# 2_MicroController.net
KiCad netlist of a schematic drawn in Altium Designer
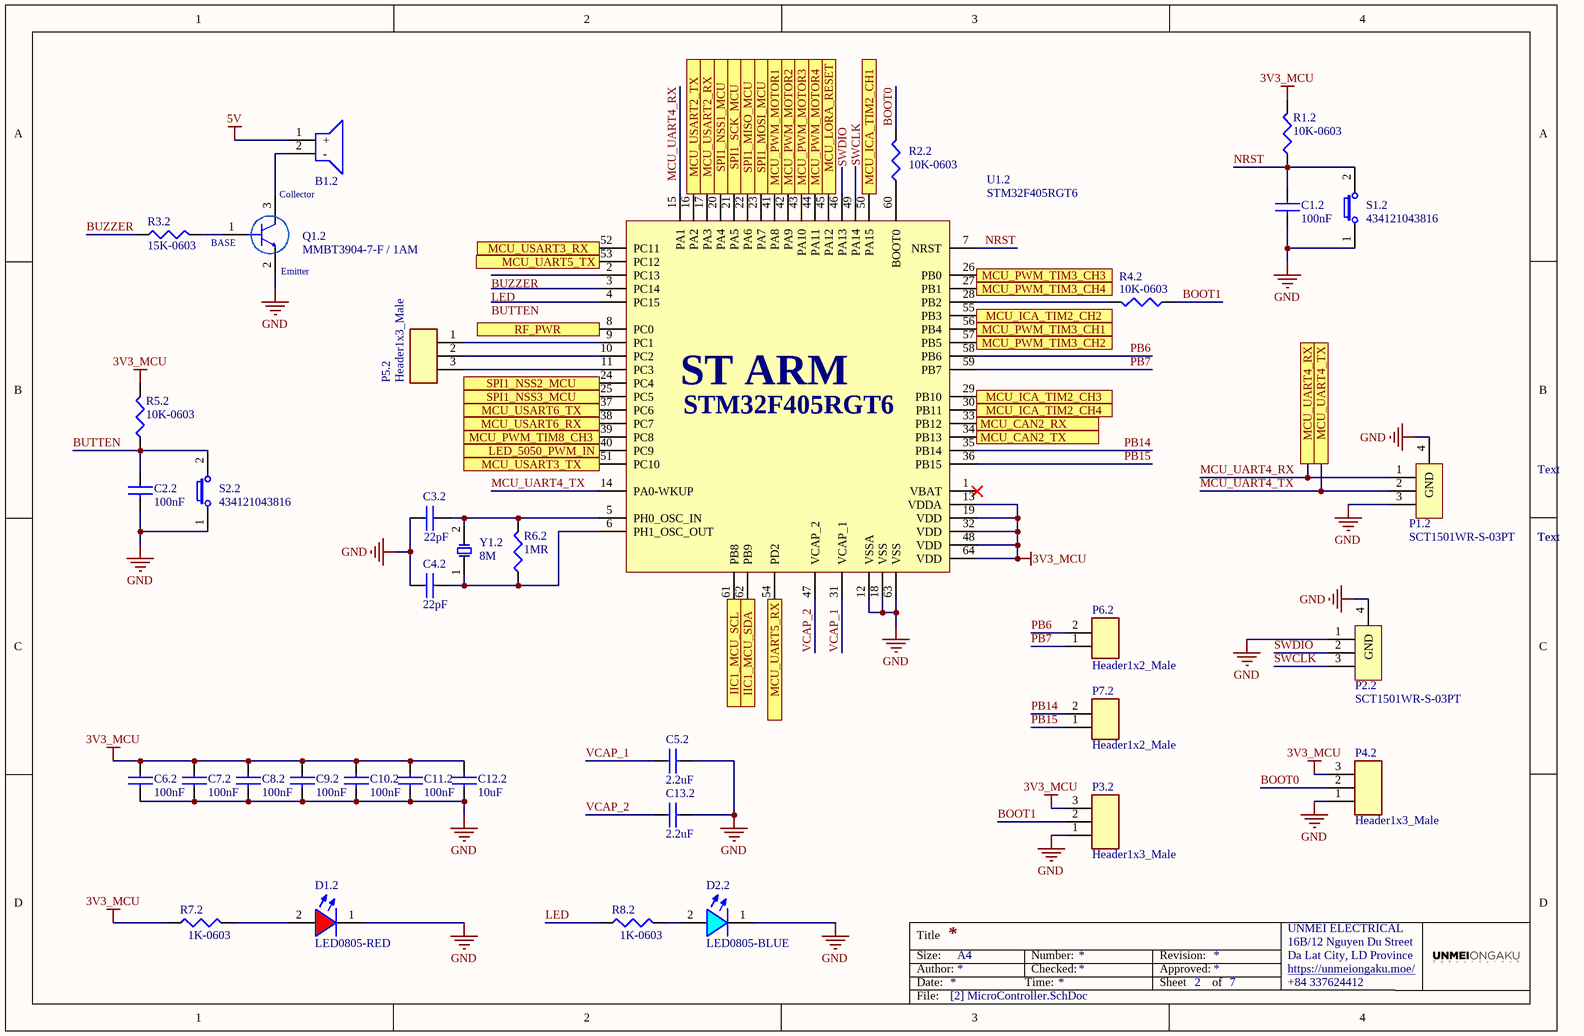
[diagram p0: [2] MicroController.SchDoc]

(export (version "E")
  (design (tool "Eeschema 10.0.6"))
  (components
    (comp (ref "B1.2")
      (value "Buzzer")
      (footprint "Buzzer 9x5mm 60dB")
      (description "9050 DIP Buzzer 9x5mm 60dB")
      (fields (field (name "LOCAL SUPPLIER PART NUMBER") "1209 DIP Buzzer 12x9mm"))
      (libsource (lib "Minh_Lib") (part "Buzzer 9050 - DIP"))
    )
    (comp (ref "C1.2")
      (value "100nF")
      (footprint "CAP0603")
      (description "CAP CER 0.1UF 50V X7R 0603")
      (fields (field (name "TOLERANCE") "±10%"))
      (libsource (lib "Minh_Lib") (part "CC0603KRX7R9BB104"))
    )
    (comp (ref "C2.2")
      (value "100nF")
      (footprint "CAP0603")
      (description "CAP CER 0.1UF 50V X7R 0603")
      (fields (field (name "TOLERANCE") "±10%"))
      (libsource (lib "Minh_Lib") (part "CC0603KRX7R9BB104"))
    )
    (comp (ref "C3.2")
      (value "22pF")
      (footprint "CAP0603")
      (description "Surface Mount Ceramic Multilayer Capacitor 22pF 5% C0G 50V 0603 Paper T/R")
      (fields
        (field (name "MANUFACTURER") "Yageo")
        (field (name "MANUFACTURER PART NUMBER") "CC0603JRNPO9BN220")
      )
      (libsource (lib "Minh_Lib") (part "CC0603JRNPO9BN220"))
    )
    (comp (ref "C4.2")
      (value "22pF")
      (footprint "CAP0603")
      (description "Surface Mount Ceramic Multilayer Capacitor 22pF 5% C0G 50V 0603 Paper T/R")
      (fields
        (field (name "MANUFACTURER") "Yageo")
        (field (name "MANUFACTURER PART NUMBER") "CC0603JRNPO9BN220")
      )
      (libsource (lib "Minh_Lib") (part "CC0603JRNPO9BN220"))
    )
    (comp (ref "C5.2")
      (value "2.2uF")
      (footprint "CAP0603")
      (description "CAP CER 2.2UF 10V X7R 0603")
      (fields (field (name "TOLERANCE") "±10%"))
      (libsource (lib "Minh_Lib") (part "CC0603KRX7R6BB225"))
    )
    (comp (ref "C6.2")
      (value "100nF")
      (footprint "CAP0603")
      (description "CAP CER 0.1UF 50V X7R 0603")
      (fields (field (name "TOLERANCE") "±10%"))
      (libsource (lib "Minh_Lib") (part "CC0603KRX7R9BB104"))
    )
    (comp (ref "C7.2")
      (value "100nF")
      (footprint "CAP0603")
      (description "CAP CER 0.1UF 50V X7R 0603")
      (fields (field (name "TOLERANCE") "±10%"))
      (libsource (lib "Minh_Lib") (part "CC0603KRX7R9BB104"))
    )
    (comp (ref "C8.2")
      (value "100nF")
      (footprint "CAP0603")
      (description "CAP CER 0.1UF 50V X7R 0603")
      (fields (field (name "TOLERANCE") "±10%"))
      (libsource (lib "Minh_Lib") (part "CC0603KRX7R9BB104"))
    )
    (comp (ref "C9.2")
      (value "100nF")
      (footprint "CAP0603")
      (description "CAP CER 0.1UF 50V X7R 0603")
      (fields (field (name "TOLERANCE") "±10%"))
      (libsource (lib "Minh_Lib") (part "CC0603KRX7R9BB104"))
    )
    (comp (ref "C10.2")
      (value "100nF")
      (footprint "CAP0603")
      (description "CAP CER 0.1UF 50V X7R 0603")
      (fields (field (name "TOLERANCE") "±10%"))
      (libsource (lib "Minh_Lib") (part "CC0603KRX7R9BB104"))
    )
    (comp (ref "C11.2")
      (value "100nF")
      (footprint "CAP0603")
      (description "CAP CER 0.1UF 50V X7R 0603")
      (fields (field (name "TOLERANCE") "±10%"))
      (libsource (lib "Minh_Lib") (part "CC0603KRX7R9BB104"))
    )
    (comp (ref "C12.2")
      (value "10uF")
      (footprint "CAP0603")
      (description "CAP CER 10UF 10V X5R 0603")
      (fields (field (name "TOLERANCE") "±10%"))
      (libsource (lib "Minh_Lib") (part "CC0603KRX5R6BB106"))
    )
    (comp (ref "C13.2")
      (value "2.2uF")
      (footprint "CAP0603")
      (description "CAP CER 2.2UF 10V X7R 0603")
      (fields (field (name "TOLERANCE") "±10%"))
      (libsource (lib "Minh_Lib") (part "CC0603KRX7R6BB225"))
    )
    (comp (ref "D1.2")
      (value "LED0805-RED")
      (footprint "LED0805-RED")
      (libsource (lib "Minh_Lib") (part "LED0805-RED"))
    )
    (comp (ref "D2.2")
      (value "LED0805-BLUE")
      (footprint "LED0805-BLUE")
      (libsource (lib "Minh_Lib") (part "LED0805-BLUE"))
    )
    (comp (ref "P1.2")
      (value "SCT1501WR-S-03PT")
      (footprint "Connector ZH1.5 3P SMD")
      (libsource (lib "Minh_Lib") (part "SCT1501WR-S-03PT"))
    )
    (comp (ref "P2.2")
      (value "SCT1501WR-S-03PT")
      (footprint "Connector ZH1.5 3P SMD")
      (libsource (lib "Minh_Lib") (part "SCT1501WR-S-03PT"))
    )
    (comp (ref "P3.2")
      (value "Header1x3_Male")
      (footprint "Minh_Lib:HDR1x3_2.54_MALE")
      (description "Header1x3_2.54_MALE")
      (libsource (lib "") (part "HDR1x3_2.54_MALE_1"))
    )
    (comp (ref "P4.2")
      (value "Header1x3_Male")
      (footprint "Minh_Lib:HDR1x3_2.54_MALE")
      (description "Header1x3_2.54_MALE")
      (libsource (lib "") (part "HDR1x3_2.54_MALE_1"))
    )
    (comp (ref "P5.2")
      (value "Header1x3_Male")
      (footprint "Minh_Lib:HDR1x3_2.54_MALE")
      (description "Header1x3_2.54_MALE")
      (libsource (lib "Minh_Lib") (part "HDR1x3_2.54_MALE"))
    )
    (comp (ref "P6.2")
      (value "Header1x2_Male")
      (footprint "Minh_Lib:HDR1x2_2.54_MALE")
      (description "Header1x2_2.54_MALE")
      (libsource (lib "Minh_Lib") (part "HDR1x2_2.54_MALE"))
    )
    (comp (ref "P7.2")
      (value "Header1x2_Male")
      (footprint "Minh_Lib:HDR1x2_2.54_MALE")
      (description "Header1x2_2.54_MALE")
      (libsource (lib "Minh_Lib") (part "HDR1x2_2.54_MALE"))
    )
    (comp (ref "Q1.2")
      (value "MMBT3904-7-F / 1AM")
      (footprint "SOT23")
      (description "Transistor General Purpose BJT NPN 40 Volt 0.2A Automotive 3-Pin SOT-23")
      (fields
        (field (name "MANUFACTURER") "Diodes Zetex")
        (field (name "MANUFACTURER PART NUMBER") "MMBT3904-7-F")
      )
      (libsource (lib "Minh_Lib") (part "MMBT3904-7-F / 1AM"))
    )
    (comp (ref "R1.2")
      (value "10K-0603")
      (footprint "RES0603 - 3D")
      (description "RES SMD 10K OHM 1% 1/10W 0603")
      (fields
        (field (name "MANUFACTURER") "Yageo")
        (field (name "MANUFACTURER PART NUMBER") "RC0603FR-0710KL")
      )
      (libsource (lib "Minh_Lib") (part "RC0603FR-0710KL"))
    )
    (comp (ref "R2.2")
      (value "10K-0603")
      (footprint "RES0603 - 3D")
      (description "RES SMD 10K OHM 1% 1/10W 0603")
      (fields
        (field (name "MANUFACTURER") "Yageo")
        (field (name "MANUFACTURER PART NUMBER") "RC0603FR-0710KL")
      )
      (libsource (lib "Minh_Lib") (part "RC0603FR-0710KL"))
    )
    (comp (ref "R3.2")
      (value "15K-0603")
      (footprint "RES0603 - 3D")
      (description "Thick Film Resistors - SMD 15K OHM 5%")
      (fields
        (field (name "MANUFACTURER") "Yageo")
        (field (name "MANUFACTURER PART NUMBER") "RC0603JR-0715KL")
      )
      (libsource (lib "Minh_Lib") (part "RC0603JR-0715KL"))
    )
    (comp (ref "R4.2")
      (value "10K-0603")
      (footprint "RES0603 - 3D")
      (description "RES SMD 10K OHM 1% 1/10W 0603")
      (fields
        (field (name "MANUFACTURER") "Yageo")
        (field (name "MANUFACTURER PART NUMBER") "RC0603FR-0710KL")
      )
      (libsource (lib "Minh_Lib") (part "RC0603FR-0710KL"))
    )
    (comp (ref "R5.2")
      (value "10K-0603")
      (footprint "RES0603 - 3D")
      (description "RES SMD 10K OHM 1% 1/10W 0603")
      (fields
        (field (name "MANUFACTURER") "Yageo")
        (field (name "MANUFACTURER PART NUMBER") "RC0603FR-0710KL")
      )
      (libsource (lib "Minh_Lib") (part "RC0603FR-0710KL"))
    )
    (comp (ref "R6.2")
      (value "1MR")
      (footprint "RES0603 - 3D")
      (description "RES SMD 1M OHM 5% 1/10W 0603")
      (fields (field (name "TOLERANCE") "±5%"))
      (libsource (lib "Minh_Lib") (part "RC0603JR-071ML"))
    )
    (comp (ref "R7.2")
      (value "1K-0603")
      (footprint "RES0603 - 3D")
      (description "RES SMD 1K OHM 5% 1/10W 0603")
      (fields (field (name "TOLERANCE") "±5%"))
      (libsource (lib "Minh_Lib") (part "RC0603JR-071KL"))
    )
    (comp (ref "R8.2")
      (value "1K-0603")
      (footprint "RES0603 - 3D")
      (description "RES SMD 1K OHM 5% 1/10W 0603")
      (fields (field (name "TOLERANCE") "±5%"))
      (libsource (lib "Minh_Lib") (part "RC0603JR-071KL"))
    )
    (comp (ref "S1.2")
      (value "434121043816")
      (footprint "Switches-6x3.5x4.3mm")
      (description "Switch Tactile Spst-no 0.05A 12V")
      (fields (field (name "MANUFACTURER") "Wurth Electronics"))
      (libsource (lib "Minh_Lib") (part "434121043816"))
    )
    (comp (ref "S2.2")
      (value "434121043816")
      (footprint "Switches-6x3.5x4.3mm")
      (description "Switch Tactile Spst-no 0.05A 12V")
      (fields (field (name "MANUFACTURER") "Wurth Electronics"))
      (libsource (lib "Minh_Lib") (part "434121043816"))
    )
    (comp (ref "U1.2")
      (value "STM32F405RGT6")
      (footprint "LQFP64")
      (description "IC MCU 32BIT 1MB FLASH 64LQFP")
      (fields (field (name "MANUFACTURER") "STMicroelectronics"))
      (libsource (lib "Minh_Lib") (part "STM32F405RGT6"))
    )
    (comp (ref "Y1.2")
      (value "8M")
      (footprint "HC49-S")
      (description "Crystals LO-PRO 8MHz")
      (fields
        (field (name "MANUFACTURER") "Fox Electronics")
        (field (name "MANUFACTURER PART NUMBER") "HC49SSDLF-8.00MHz")
      )
      (libsource (lib "Minh_Lib") (part "Crystals - HC49SSDLF-8.00MHz"))
    )
  )
  (nets
    (net (code "1") (name "/BOOT0") (class "Default")
      (node (ref "P4.2") (pin "2") (pinfunction "2_2") (pintype "passive"))
      (node (ref "R2.2") (pin "2") (pinfunction "2_2") (pintype "passive"))
    )
    (net (code "2") (name "/BOOT1") (class "Default")
      (node (ref "P3.2") (pin "2") (pinfunction "2_2") (pintype "passive"))
      (node (ref "R4.2") (pin "1") (pinfunction "1_1") (pintype "passive"))
    )
    (net (code "3") (name "/BUTTEN") (class "Default")
      (node (ref "C2.2") (pin "1") (pinfunction "1_1") (pintype "passive"))
      (node (ref "R5.2") (pin "1") (pinfunction "1_1") (pintype "passive"))
      (node (ref "S2.2") (pin "2") (pinfunction "2_2") (pintype "passive"))
      (node (ref "U1.2") (pin "4") (pinfunction "PC15_4") (pintype "passive"))
    )
    (net (code "4") (name "/BUZZER") (class "Default")
      (node (ref "R3.2") (pin "1") (pinfunction "1_1") (pintype "passive"))
      (node (ref "U1.2") (pin "2") (pinfunction "PC13_2") (pintype "passive"))
    )
    (net (code "5") (name "/IIC1_MCU_SCL") (class "Default")
      (node (ref "U1.2") (pin "61") (pinfunction "PB8_61") (pintype "passive"))
    )
    (net (code "6") (name "/IIC1_MCU_SDA") (class "Default")
      (node (ref "U1.2") (pin "62") (pinfunction "PB9_62") (pintype "passive"))
    )
    (net (code "7") (name "/LED") (class "Default")
      (node (ref "R8.2") (pin "1") (pinfunction "1_1") (pintype "passive"))
      (node (ref "U1.2") (pin "3") (pinfunction "PC14_3") (pintype "passive"))
    )
    (net (code "8") (name "/LED_5050_PWM_IN") (class "Default")
      (node (ref "U1.2") (pin "40") (pinfunction "PC9_40") (pintype "passive"))
    )
    (net (code "24") (name "/MCU_PWM_TIM8_CH3") (class "Default")
      (node (ref "U1.2") (pin "39") (pinfunction "PC8_39") (pintype "passive"))
    )
    (net (code "25") (name "/MCU_UART4_RX") (class "Default")
      (node (ref "P1.2") (pin "1") (pinfunction "1_1") (pintype "passive"))
      (node (ref "U1.2") (pin "15") (pinfunction "PA1_15") (pintype "passive"))
    )
    (net (code "26") (name "/MCU_UART4_TX") (class "Default")
      (node (ref "P1.2") (pin "2") (pinfunction "2_2") (pintype "passive"))
      (node (ref "U1.2") (pin "14") (pinfunction "PA0-WKUP_14") (pintype "passive"))
    )
    (net (code "27") (name "/MCU_UART5_RX") (class "Default")
      (node (ref "U1.2") (pin "54") (pinfunction "PD2_54") (pintype "passive"))
    )
    (net (code "28") (name "/MCU_UART5_TX") (class "Default")
      (node (ref "U1.2") (pin "53") (pinfunction "PC12_53") (pintype "passive"))
    )
    (net (code "31") (name "/MCU_USART3_RX") (class "Default")
      (node (ref "U1.2") (pin "52") (pinfunction "PC11_52") (pintype "passive"))
    )
    (net (code "32") (name "/MCU_USART3_TX") (class "Default")
      (node (ref "U1.2") (pin "51") (pinfunction "PC10_51") (pintype "passive"))
    )
    (net (code "33") (name "/MCU_USART6_RX") (class "Default")
      (node (ref "U1.2") (pin "38") (pinfunction "PC7_38") (pintype "passive"))
    )
    (net (code "34") (name "/MCU_USART6_TX") (class "Default")
      (node (ref "U1.2") (pin "37") (pinfunction "PC6_37") (pintype "passive"))
    )
    (net (code "35") (name "/NRST") (class "Default")
      (node (ref "C1.2") (pin "1") (pinfunction "1_1") (pintype "passive"))
      (node (ref "R1.2") (pin "1") (pinfunction "1_1") (pintype "passive"))
      (node (ref "S1.2") (pin "2") (pinfunction "2_2") (pintype "passive"))
      (node (ref "U1.2") (pin "7") (pinfunction "NRST_7") (pintype "passive"))
    )
    (net (code "36") (name "/PB6") (class "Default")
      (node (ref "P6.2") (pin "2") (pinfunction "2_2") (pintype "passive"))
      (node (ref "U1.2") (pin "58") (pinfunction "PB6_58") (pintype "passive"))
    )
    (net (code "37") (name "/PB7") (class "Default")
      (node (ref "P6.2") (pin "1") (pinfunction "1_1") (pintype "passive"))
      (node (ref "U1.2") (pin "59") (pinfunction "PB7_59") (pintype "passive"))
    )
    (net (code "38") (name "/PB14") (class "Default")
      (node (ref "P7.2") (pin "2") (pinfunction "2_2") (pintype "passive"))
      (node (ref "U1.2") (pin "35") (pinfunction "PB14_35") (pintype "passive"))
    )
    (net (code "39") (name "/PB15") (class "Default")
      (node (ref "P7.2") (pin "1") (pinfunction "1_1") (pintype "passive"))
      (node (ref "U1.2") (pin "36") (pinfunction "PB15_36") (pintype "passive"))
    )
    (net (code "40") (name "/RF_PWR") (class "Default")
      (node (ref "U1.2") (pin "8") (pinfunction "PC0_8") (pintype "passive"))
    )
    (net (code "44") (name "/SPI1_NSS2_MCU") (class "Default")
      (node (ref "U1.2") (pin "24") (pinfunction "PC4_24") (pintype "passive"))
    )
    (net (code "45") (name "/SPI1_NSS3_MCU") (class "Default")
      (node (ref "U1.2") (pin "25") (pinfunction "PC5_25") (pintype "passive"))
    )
    (net (code "47") (name "/SWCLK") (class "Default")
      (node (ref "P2.2") (pin "3") (pinfunction "3_3") (pintype "passive"))
      (node (ref "U1.2") (pin "49") (pinfunction "PA14_49") (pintype "passive"))
    )
    (net (code "48") (name "/SWDIO") (class "Default")
      (node (ref "P2.2") (pin "2") (pinfunction "2_2") (pintype "passive"))
      (node (ref "U1.2") (pin "46") (pinfunction "PA13_46") (pintype "passive"))
    )
    (net (code "49") (name "/VCAP_1") (class "Default")
      (node (ref "C5.2") (pin "1") (pinfunction "1_1") (pintype "passive"))
      (node (ref "U1.2") (pin "31") (pinfunction "VCAP_1_31") (pintype "passive"))
    )
    (net (code "50") (name "/VCAP_2") (class "Default")
      (node (ref "C13.2") (pin "1") (pinfunction "1_1") (pintype "passive"))
      (node (ref "U1.2") (pin "47") (pinfunction "VCAP_2_47") (pintype "passive"))
    )
    (net (code "51") (name "3V3_MCU") (class "Default")
      (node (ref "C10.2") (pin "1") (pinfunction "1_1") (pintype "passive"))
      (node (ref "C11.2") (pin "1") (pinfunction "1_1") (pintype "passive"))
      (node (ref "C12.2") (pin "1") (pinfunction "1_1") (pintype "passive"))
      (node (ref "C6.2") (pin "1") (pinfunction "1_1") (pintype "passive"))
      (node (ref "C7.2") (pin "1") (pinfunction "1_1") (pintype "passive"))
      (node (ref "C8.2") (pin "1") (pinfunction "1_1") (pintype "passive"))
      (node (ref "C9.2") (pin "1") (pinfunction "1_1") (pintype "passive"))
      (node (ref "P3.2") (pin "3") (pinfunction "3_3") (pintype "passive"))
      (node (ref "P4.2") (pin "3") (pinfunction "3_3") (pintype "passive"))
      (node (ref "R1.2") (pin "2") (pinfunction "2_2") (pintype "passive"))
      (node (ref "R5.2") (pin "2") (pinfunction "2_2") (pintype "passive"))
      (node (ref "R7.2") (pin "1") (pinfunction "1_1") (pintype "passive"))
      (node (ref "U1.2") (pin "13") (pinfunction "VDDA_13") (pintype "passive"))
      (node (ref "U1.2") (pin "19") (pinfunction "VDD_19") (pintype "passive"))
      (node (ref "U1.2") (pin "32") (pinfunction "VDD_32") (pintype "passive"))
      (node (ref "U1.2") (pin "48") (pinfunction "VDD_48") (pintype "passive"))
      (node (ref "U1.2") (pin "64") (pinfunction "VDD_64") (pintype "passive"))
    )
    (net (code "52") (name "5V") (class "Default")
      (node (ref "B1.2") (pin "1") (pinfunction "+_1") (pintype "passive"))
    )
    (net (code "53") (name "GND") (class "Default")
      (node (ref "C1.2") (pin "2") (pinfunction "2_2") (pintype "passive"))
      (node (ref "C10.2") (pin "2") (pinfunction "2_2") (pintype "passive"))
      (node (ref "C11.2") (pin "2") (pinfunction "2_2") (pintype "passive"))
      (node (ref "C12.2") (pin "2") (pinfunction "2_2") (pintype "passive"))
      (node (ref "C13.2") (pin "2") (pinfunction "2_2") (pintype "passive"))
      (node (ref "C2.2") (pin "2") (pinfunction "2_2") (pintype "passive"))
      (node (ref "C3.2") (pin "1") (pinfunction "1_1") (pintype "passive"))
      (node (ref "C4.2") (pin "1") (pinfunction "1_1") (pintype "passive"))
      (node (ref "C5.2") (pin "2") (pinfunction "2_2") (pintype "passive"))
      (node (ref "C6.2") (pin "2") (pinfunction "2_2") (pintype "passive"))
      (node (ref "C7.2") (pin "2") (pinfunction "2_2") (pintype "passive"))
      (node (ref "C8.2") (pin "2") (pinfunction "2_2") (pintype "passive"))
      (node (ref "C9.2") (pin "2") (pinfunction "2_2") (pintype "passive"))
      (node (ref "D1.2") (pin "1") (pinfunction "+_1") (pintype "passive"))
      (node (ref "D2.2") (pin "1") (pinfunction "+_1") (pintype "passive"))
      (node (ref "P1.2") (pin "3") (pinfunction "3_3") (pintype "passive"))
      (node (ref "P1.2") (pin "4") (pinfunction "GND_4") (pintype "passive"))
      (node (ref "P2.2") (pin "1") (pinfunction "1_1") (pintype "passive"))
      (node (ref "P2.2") (pin "4") (pinfunction "GND_4") (pintype "passive"))
      (node (ref "P3.2") (pin "1") (pinfunction "1_1") (pintype "passive"))
      (node (ref "P4.2") (pin "1") (pinfunction "1_1") (pintype "passive"))
      (node (ref "Q1.2") (pin "2") (pinfunction "2_2") (pintype "passive"))
      (node (ref "S1.2") (pin "1") (pinfunction "1_1") (pintype "passive"))
      (node (ref "S2.2") (pin "1") (pinfunction "1_1") (pintype "passive"))
      (node (ref "U1.2") (pin "12") (pinfunction "VSSA_12") (pintype "passive"))
      (node (ref "U1.2") (pin "18") (pinfunction "VSS_18") (pintype "passive"))
      (node (ref "U1.2") (pin "63") (pinfunction "VSS_63") (pintype "passive"))
    )
    (net (code "54") (name "Net-(B1.2--)") (class "Default")
      (node (ref "B1.2") (pin "2") (pinfunction "-_2") (pintype "passive"))
      (node (ref "Q1.2") (pin "3") (pinfunction "3_3") (pintype "passive"))
    )
    (net (code "55") (name "Net-(D1.2-+-Pad2)") (class "Default")
      (node (ref "D1.2") (pin "2") (pinfunction "+_2") (pintype "passive"))
      (node (ref "R7.2") (pin "2") (pinfunction "2_2") (pintype "passive"))
    )
    (net (code "56") (name "Net-(D2.2-+-Pad2)") (class "Default")
      (node (ref "D2.2") (pin "2") (pinfunction "+_2") (pintype "passive"))
      (node (ref "R8.2") (pin "2") (pinfunction "2_2") (pintype "passive"))
    )
    (net (code "57") (name "Net-(Q1.2-Pad1)") (class "Default")
      (node (ref "Q1.2") (pin "1") (pinfunction "1_1") (pintype "passive"))
      (node (ref "R3.2") (pin "2") (pinfunction "2_2") (pintype "passive"))
    )
    (net (code "58") (name "Net-(U1.2-BOOT0)") (class "Default")
      (node (ref "R2.2") (pin "1") (pinfunction "1_1") (pintype "passive"))
      (node (ref "U1.2") (pin "60") (pinfunction "BOOT0_60") (pintype "passive"))
    )
    (net (code "59") (name "Net-(U1.2-PB2)") (class "Default")
      (node (ref "R4.2") (pin "2") (pinfunction "2_2") (pintype "passive"))
      (node (ref "U1.2") (pin "28") (pinfunction "PB2_28") (pintype "passive"))
    )
    (net (code "60") (name "Net-(U1.2-PC1)") (class "Default")
      (node (ref "P5.2") (pin "1") (pinfunction "1_1") (pintype "passive"))
      (node (ref "U1.2") (pin "9") (pinfunction "PC1_9") (pintype "passive"))
    )
    (net (code "61") (name "Net-(U1.2-PC2)") (class "Default")
      (node (ref "P5.2") (pin "2") (pinfunction "2_2") (pintype "passive"))
      (node (ref "U1.2") (pin "10") (pinfunction "PC2_10") (pintype "passive"))
    )
    (net (code "62") (name "Net-(U1.2-PC3)") (class "Default")
      (node (ref "P5.2") (pin "3") (pinfunction "3_3") (pintype "passive"))
      (node (ref "U1.2") (pin "11") (pinfunction "PC3_11") (pintype "passive"))
    )
    (net (code "63") (name "Net-(U1.2-PH0_OSC_IN)") (class "Default")
      (node (ref "C3.2") (pin "2") (pinfunction "2_2") (pintype "passive"))
      (node (ref "R6.2") (pin "2") (pinfunction "2_2") (pintype "passive"))
      (node (ref "U1.2") (pin "5") (pinfunction "PH0_OSC_IN_5") (pintype "passive"))
      (node (ref "Y1.2") (pin "2") (pinfunction "7_2") (pintype "passive"))
    )
    (net (code "64") (name "Net-(U1.2-PH1_OSC_OUT)") (class "Default")
      (node (ref "C4.2") (pin "2") (pinfunction "2_2") (pintype "passive"))
      (node (ref "R6.2") (pin "1") (pinfunction "1_1") (pintype "passive"))
      (node (ref "U1.2") (pin "6") (pinfunction "PH1_OSC_OUT_6") (pintype "passive"))
      (node (ref "Y1.2") (pin "1") (pinfunction "6_1") (pintype "passive"))
    )
    (net (code "65") (name "unconnected-(U1.2-PA2-Pad16)") (class "Default")
      (node (ref "U1.2") (pin "16") (pinfunction "PA2_16") (pintype "passive"))
    )
    (net (code "66") (name "unconnected-(U1.2-PA3-Pad17)") (class "Default")
      (node (ref "U1.2") (pin "17") (pinfunction "PA3_17") (pintype "passive"))
    )
    (net (code "67") (name "unconnected-(U1.2-PA4-Pad20)") (class "Default")
      (node (ref "U1.2") (pin "20") (pinfunction "PA4_20") (pintype "passive"))
    )
    (net (code "68") (name "unconnected-(U1.2-PA5-Pad21)") (class "Default")
      (node (ref "U1.2") (pin "21") (pinfunction "PA5_21") (pintype "passive"))
    )
    (net (code "69") (name "unconnected-(U1.2-PA6-Pad22)") (class "Default")
      (node (ref "U1.2") (pin "22") (pinfunction "PA6_22") (pintype "passive"))
    )
    (net (code "70") (name "unconnected-(U1.2-PA7-Pad23)") (class "Default")
      (node (ref "U1.2") (pin "23") (pinfunction "PA7_23") (pintype "passive"))
    )
    (net (code "71") (name "unconnected-(U1.2-PA8-Pad41)") (class "Default")
      (node (ref "U1.2") (pin "41") (pinfunction "PA8_41") (pintype "passive"))
    )
    (net (code "72") (name "unconnected-(U1.2-PA9-Pad42)") (class "Default")
      (node (ref "U1.2") (pin "42") (pinfunction "PA9_42") (pintype "passive"))
    )
    (net (code "73") (name "unconnected-(U1.2-PA10-Pad43)") (class "Default")
      (node (ref "U1.2") (pin "43") (pinfunction "PA10_43") (pintype "passive"))
    )
    (net (code "74") (name "unconnected-(U1.2-PA11-Pad44)") (class "Default")
      (node (ref "U1.2") (pin "44") (pinfunction "PA11_44") (pintype "passive"))
    )
    (net (code "75") (name "unconnected-(U1.2-PA12-Pad45)") (class "Default")
      (node (ref "U1.2") (pin "45") (pinfunction "PA12_45") (pintype "passive"))
    )
    (net (code "76") (name "unconnected-(U1.2-PA15-Pad50)") (class "Default")
      (node (ref "U1.2") (pin "50") (pinfunction "PA15_50") (pintype "passive"))
    )
    (net (code "77") (name "unconnected-(U1.2-PB0-Pad26)") (class "Default")
      (node (ref "U1.2") (pin "26") (pinfunction "PB0_26") (pintype "passive"))
    )
    (net (code "78") (name "unconnected-(U1.2-PB1-Pad27)") (class "Default")
      (node (ref "U1.2") (pin "27") (pinfunction "PB1_27") (pintype "passive"))
    )
    (net (code "79") (name "unconnected-(U1.2-PB3-Pad55)") (class "Default")
      (node (ref "U1.2") (pin "55") (pinfunction "PB3_55") (pintype "passive"))
    )
    (net (code "80") (name "unconnected-(U1.2-PB4-Pad56)") (class "Default")
      (node (ref "U1.2") (pin "56") (pinfunction "PB4_56") (pintype "passive"))
    )
    (net (code "81") (name "unconnected-(U1.2-PB5-Pad57)") (class "Default")
      (node (ref "U1.2") (pin "57") (pinfunction "PB5_57") (pintype "passive"))
    )
    (net (code "82") (name "unconnected-(U1.2-PB10-Pad29)") (class "Default")
      (node (ref "U1.2") (pin "29") (pinfunction "PB10_29") (pintype "passive"))
    )
    (net (code "83") (name "unconnected-(U1.2-PB11-Pad30)") (class "Default")
      (node (ref "U1.2") (pin "30") (pinfunction "PB11_30") (pintype "passive"))
    )
    (net (code "84") (name "unconnected-(U1.2-PB12-Pad33)") (class "Default")
      (node (ref "U1.2") (pin "33") (pinfunction "PB12_33") (pintype "passive"))
    )
    (net (code "85") (name "unconnected-(U1.2-PB13-Pad34)") (class "Default")
      (node (ref "U1.2") (pin "34") (pinfunction "PB13_34") (pintype "passive"))
    )
    (net (code "86") (name "unconnected-(U1.2-VBAT-Pad1)") (class "Default")
      (node (ref "U1.2") (pin "1") (pinfunction "VBAT_1") (pintype "passive+no_connect"))
    )
  )
)
